# Net_Widget.net
KiCad netlist of a schematic drawn in EAGLE
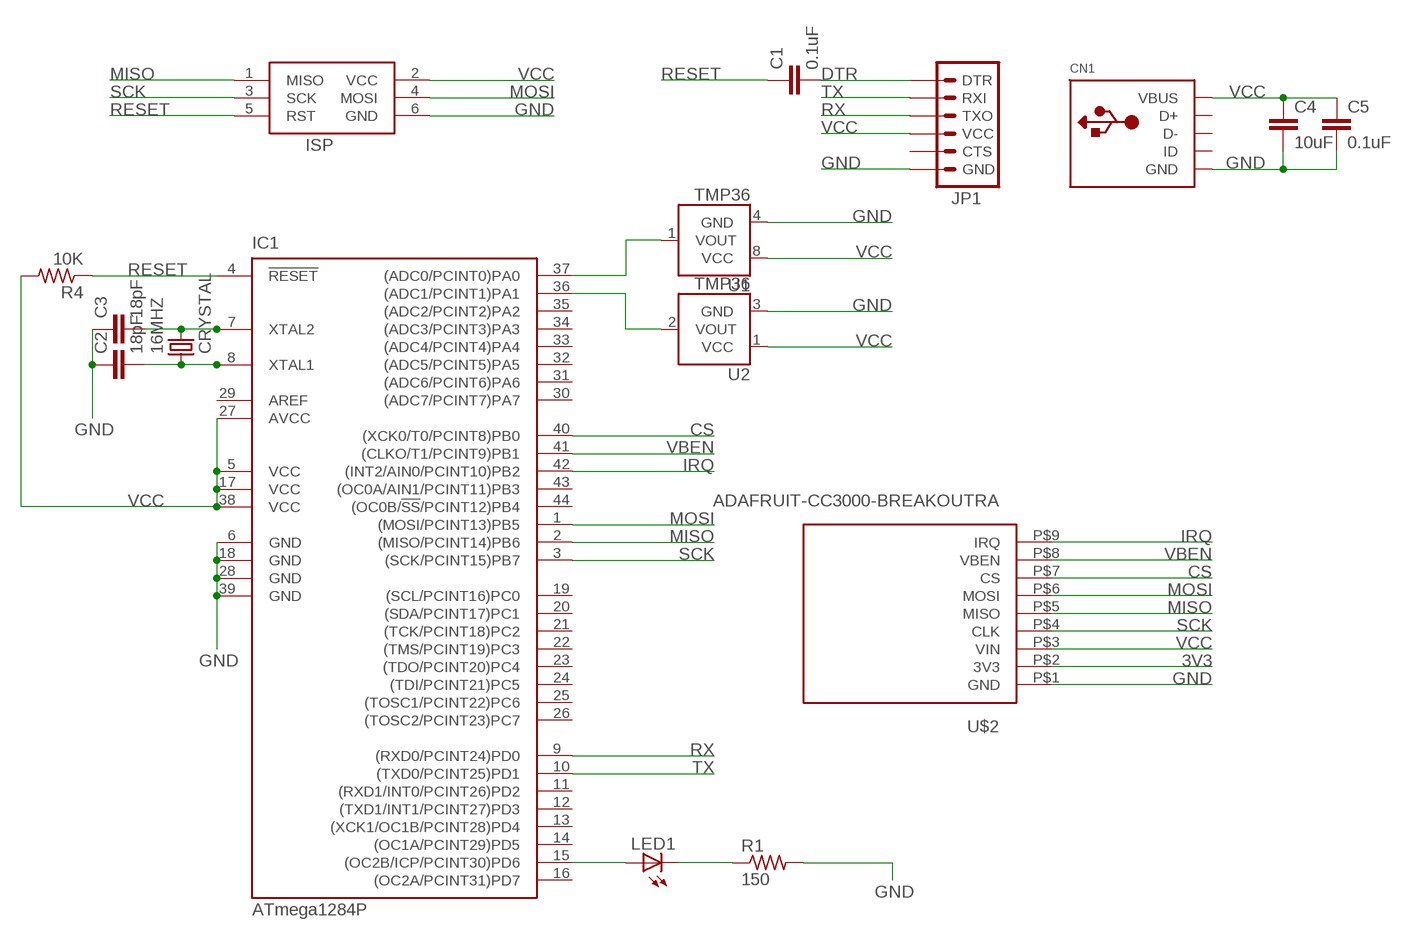
[diagram p0: schematic, sheet 1]

(export (version "E")
  (design (tool "Eeschema 10.0.6"))
  (components
    (comp (ref "16MHZ")
      (value "CRYSTAL")
      (footprint "eagle-import:2-SMD-5X3MM")
      (libsource (lib "eagle-import") (part "CRYSTAL"))
    )
    (comp (ref "C1")
      (value "0.1uF")
      (footprint "eagle-import:C1206")
      (libsource (lib "eagle-import") (part "C-EUC1206"))
    )
    (comp (ref "C2")
      (value "18pF")
      (footprint "eagle-import:C1206")
      (libsource (lib "eagle-import") (part "C-EUC1206"))
    )
    (comp (ref "C3")
      (value "18pF")
      (footprint "eagle-import:C1206")
      (libsource (lib "eagle-import") (part "C-EUC1206"))
    )
    (comp (ref "C4")
      (value "10uF")
      (footprint "eagle-import:C1206")
      (libsource (lib "eagle-import") (part "C-EUC1206"))
    )
    (comp (ref "C5")
      (value "0.1uF")
      (footprint "eagle-import:C1206")
      (libsource (lib "eagle-import") (part "C-EUC1206"))
    )
    (comp (ref "CN1")
      (value "USBPWR")
      (footprint "eagle-import:USB-MINIB-POWER")
      (libsource (lib "eagle-import") (part "USBPWR"))
    )
    (comp (ref "IC1")
      (value "ATmega1284P")
      (footprint "eagle-import:TQFP44")
      (libsource (lib "eagle-import") (part "MEGA164P/324P/644P-AU"))
    )
    (comp (ref "ISP")
      (value "AVRISP-6")
      (footprint "eagle-import:AVRISP")
      (libsource (lib "eagle-import") (part "AVRISP-6"))
    )
    (comp (ref "JP1")
      (value "ARDUINO_SERIAL_PROGRAMSMD")
      (footprint "eagle-import:1X06-SMD")
      (libsource (lib "eagle-import") (part "ARDUINO_SERIAL_PROGRAMSMD"))
    )
    (comp (ref "LED1")
      (value "LEDSMT1206")
      (footprint "eagle-import:1206")
      (libsource (lib "eagle-import") (part "LEDSMT1206"))
    )
    (comp (ref "R1")
      (value "150")
      (footprint "eagle-import:R1206")
      (libsource (lib "eagle-import") (part "R-US_R1206"))
    )
    (comp (ref "R4")
      (value "10K")
      (footprint "eagle-import:R1206")
      (libsource (lib "eagle-import") (part "R-US_R1206"))
    )
    (comp (ref "U$2")
      (value "ADAFRUIT-CC3000-BREAKOUTRA")
      (footprint "eagle-import:ADAFRUIT-CC3000-BREAKOUT-RA")
      (libsource (lib "eagle-import") (part "ADAFRUIT-CC3000-BREAKOUTRA"))
    )
    (comp (ref "U1")
      (value "TMP36")
      (footprint "eagle-import:SO08")
      (libsource (lib "eagle-import") (part "TMP36"))
    )
    (comp (ref "U2")
      (value "TMP36")
      (footprint "eagle-import:TO-92")
      (libsource (lib "eagle-import") (part "TMP36GT9"))
    )
  )
  (nets
    (net (code "1") (name "/3V3") (class "Default")
      (node (ref "U$2") (pin "P$2") (pinfunction "3V3_P$2") (pintype "bidirectional"))
    )
    (net (code "2") (name "/AREF") (class "Default")
      (node (ref "IC1") (pin "29") (pinfunction "AREF_29") (pintype "power_in"))
    )
    (net (code "3") (name "/CS") (class "Default")
      (node (ref "IC1") (pin "40") (pinfunction "(XCK0/T0/PCINT8)PB0_40") (pintype "bidirectional"))
      (node (ref "U$2") (pin "P$7") (pinfunction "CS_P$7") (pintype "bidirectional"))
    )
    (net (code "4") (name "/DTR") (class "Default")
      (node (ref "C1") (pin "2") (pinfunction "2_2") (pintype "passive"))
      (node (ref "JP1") (pin "1") (pinfunction "DTR_1") (pintype "passive"))
    )
    (net (code "5") (name "/GND") (class "Default")
      (node (ref "C2") (pin "1") (pinfunction "1_1") (pintype "passive"))
      (node (ref "C3") (pin "1") (pinfunction "1_1") (pintype "passive"))
      (node (ref "C4") (pin "2") (pinfunction "2_2") (pintype "passive"))
      (node (ref "C5") (pin "2") (pinfunction "2_2") (pintype "passive"))
      (node (ref "CN1") (pin "GND") (pinfunction "GND_GND") (pintype "power_in"))
      (node (ref "IC1") (pin "18") (pinfunction "GND_18") (pintype "power_in"))
      (node (ref "IC1") (pin "28") (pinfunction "GND_28") (pintype "power_in"))
      (node (ref "IC1") (pin "39") (pinfunction "GND_39") (pintype "power_in"))
      (node (ref "IC1") (pin "6") (pinfunction "GND_6") (pintype "power_in"))
      (node (ref "ISP") (pin "6") (pinfunction "GND_6") (pintype "power_in"))
      (node (ref "JP1") (pin "6") (pinfunction "GND_6") (pintype "passive"))
      (node (ref "R1") (pin "2") (pinfunction "2_2") (pintype "passive"))
      (node (ref "U$2") (pin "P$1") (pinfunction "GND_P$1") (pintype "bidirectional"))
      (node (ref "U1") (pin "4") (pinfunction "GND_4") (pintype "bidirectional"))
      (node (ref "U2") (pin "3") (pinfunction "GND_3") (pintype "bidirectional"))
    )
    (net (code "6") (name "/IRQ") (class "Default")
      (node (ref "IC1") (pin "42") (pinfunction "(INT2/AIN0/PCINT10)PB2_42") (pintype "bidirectional"))
      (node (ref "U$2") (pin "P$9") (pinfunction "IRQ_P$9") (pintype "bidirectional"))
    )
    (net (code "7") (name "/MISO") (class "Default")
      (node (ref "IC1") (pin "2") (pinfunction "(MISO/PCINT14)PB6_2") (pintype "bidirectional"))
      (node (ref "ISP") (pin "1") (pinfunction "MISO_1") (pintype "input"))
      (node (ref "U$2") (pin "P$5") (pinfunction "MISO_P$5") (pintype "bidirectional"))
    )
    (net (code "8") (name "/MOSI") (class "Default")
      (node (ref "IC1") (pin "1") (pinfunction "(MOSI/PCINT13)PB5_1") (pintype "bidirectional"))
      (node (ref "ISP") (pin "4") (pinfunction "MOSI_4") (pintype "output"))
      (node (ref "U$2") (pin "P$6") (pinfunction "MOSI_P$6") (pintype "bidirectional"))
    )
    (net (code "9") (name "/RESET") (class "Default")
      (node (ref "C1") (pin "1") (pinfunction "1_1") (pintype "passive"))
      (node (ref "IC1") (pin "4") (pinfunction "~{RESET}_4") (pintype "input"))
      (node (ref "ISP") (pin "5") (pinfunction "RST_5") (pintype "output"))
      (node (ref "R4") (pin "1") (pinfunction "1_1") (pintype "passive"))
    )
    (net (code "10") (name "/RX") (class "Default")
      (node (ref "IC1") (pin "9") (pinfunction "(RXD0/PCINT24)PD0_9") (pintype "bidirectional"))
      (node (ref "JP1") (pin "3") (pinfunction "TXO_3") (pintype "passive"))
    )
    (net (code "11") (name "/SCK") (class "Default")
      (node (ref "IC1") (pin "3") (pinfunction "(SCK/PCINT15)PB7_3") (pintype "bidirectional"))
      (node (ref "ISP") (pin "3") (pinfunction "SCK_3") (pintype "output"))
      (node (ref "U$2") (pin "P$4") (pinfunction "CLK_P$4") (pintype "bidirectional"))
    )
    (net (code "12") (name "/TX") (class "Default")
      (node (ref "IC1") (pin "10") (pinfunction "(TXD0/PCINT25)PD1_10") (pintype "bidirectional"))
      (node (ref "JP1") (pin "2") (pinfunction "RXI_2") (pintype "passive"))
    )
    (net (code "13") (name "/VBEN") (class "Default")
      (node (ref "IC1") (pin "41") (pinfunction "(CLKO/T1/PCINT9)PB1_41") (pintype "bidirectional"))
      (node (ref "U$2") (pin "P$8") (pinfunction "VBEN_P$8") (pintype "bidirectional"))
    )
    (net (code "14") (name "/VCC") (class "Default")
      (node (ref "C4") (pin "1") (pinfunction "1_1") (pintype "passive"))
      (node (ref "C5") (pin "1") (pinfunction "1_1") (pintype "passive"))
      (node (ref "CN1") (pin "VBUS") (pinfunction "VBUS_VBUS") (pintype "power_in"))
      (node (ref "IC1") (pin "17") (pinfunction "VCC_17") (pintype "power_in"))
      (node (ref "IC1") (pin "27") (pinfunction "AVCC_27") (pintype "power_in"))
      (node (ref "IC1") (pin "38") (pinfunction "VCC_38") (pintype "power_in"))
      (node (ref "IC1") (pin "5") (pinfunction "VCC_5") (pintype "power_in"))
      (node (ref "ISP") (pin "2") (pinfunction "VCC_2") (pintype "power_in"))
      (node (ref "JP1") (pin "4") (pinfunction "VCC_4") (pintype "passive"))
      (node (ref "R4") (pin "2") (pinfunction "2_2") (pintype "passive"))
      (node (ref "U$2") (pin "P$3") (pinfunction "VIN_P$3") (pintype "bidirectional"))
      (node (ref "U1") (pin "8") (pinfunction "VCC_8") (pintype "bidirectional"))
      (node (ref "U2") (pin "1") (pinfunction "VCC_1") (pintype "bidirectional"))
    )
    (net (code "15") (name "Net-(16MHZ-1)") (class "Default")
      (node (ref "16MHZ") (pin "P$1") (pinfunction "1_P$1") (pintype "passive"))
      (node (ref "C2") (pin "2") (pinfunction "2_2") (pintype "passive"))
      (node (ref "IC1") (pin "8") (pinfunction "XTAL1_8") (pintype "input"))
    )
    (net (code "16") (name "Net-(16MHZ-2)") (class "Default")
      (node (ref "16MHZ") (pin "P$2") (pinfunction "2_P$2") (pintype "passive"))
      (node (ref "C3") (pin "2") (pinfunction "2_2") (pintype "passive"))
      (node (ref "IC1") (pin "7") (pinfunction "XTAL2_7") (pintype "output"))
    )
    (net (code "17") (name "Net-(IC1-(ADC0{slash}PCINT0)PA0)") (class "Default")
      (node (ref "IC1") (pin "37") (pinfunction "(ADC0/PCINT0)PA0_37") (pintype "bidirectional"))
      (node (ref "U1") (pin "1") (pinfunction "VOUT_1") (pintype "bidirectional"))
    )
    (net (code "18") (name "Net-(IC1-(ADC1{slash}PCINT1)PA1)") (class "Default")
      (node (ref "IC1") (pin "36") (pinfunction "(ADC1/PCINT1)PA1_36") (pintype "bidirectional"))
      (node (ref "U2") (pin "2") (pinfunction "VOUT_2") (pintype "bidirectional"))
    )
    (net (code "19") (name "Net-(IC1-(OC2B{slash}ICP{slash}PCINT30)PD6)") (class "Default")
      (node (ref "IC1") (pin "15") (pinfunction "(OC2B/ICP/PCINT30)PD6_15") (pintype "bidirectional"))
      (node (ref "LED1") (pin "A") (pinfunction "A_A") (pintype "passive"))
    )
    (net (code "20") (name "Net-(LED1-PadC)") (class "Default")
      (node (ref "LED1") (pin "C") (pinfunction "C_C") (pintype "passive"))
      (node (ref "R1") (pin "1") (pinfunction "1_1") (pintype "passive"))
    )
    (net (code "21") (name "unconnected-(CN1-PadD+)") (class "Default")
      (node (ref "CN1") (pin "D+") (pinfunction "D+_D+") (pintype "bidirectional"))
    )
    (net (code "22") (name "unconnected-(CN1-PadD-)") (class "Default")
      (node (ref "CN1") (pin "D-") (pinfunction "D-_D-") (pintype "bidirectional"))
    )
    (net (code "23") (name "unconnected-(CN1-PadID)") (class "Default")
      (node (ref "CN1") (pin "ID") (pinfunction "ID_ID") (pintype "bidirectional"))
    )
    (net (code "24") (name "unconnected-(IC1-(ADC2{slash}PCINT2)PA2-Pad35)") (class "Default")
      (node (ref "IC1") (pin "35") (pinfunction "(ADC2/PCINT2)PA2_35") (pintype "bidirectional"))
    )
    (net (code "25") (name "unconnected-(IC1-(ADC3{slash}PCINT3)PA3-Pad34)") (class "Default")
      (node (ref "IC1") (pin "34") (pinfunction "(ADC3/PCINT3)PA3_34") (pintype "bidirectional"))
    )
    (net (code "26") (name "unconnected-(IC1-(ADC4{slash}PCINT4)PA4-Pad33)") (class "Default")
      (node (ref "IC1") (pin "33") (pinfunction "(ADC4/PCINT4)PA4_33") (pintype "bidirectional"))
    )
    (net (code "27") (name "unconnected-(IC1-(ADC5{slash}PCINT5)PA5-Pad32)") (class "Default")
      (node (ref "IC1") (pin "32") (pinfunction "(ADC5/PCINT5)PA5_32") (pintype "bidirectional"))
    )
    (net (code "28") (name "unconnected-(IC1-(ADC6{slash}PCINT6)PA6-Pad31)") (class "Default")
      (node (ref "IC1") (pin "31") (pinfunction "(ADC6/PCINT6)PA6_31") (pintype "bidirectional"))
    )
    (net (code "29") (name "unconnected-(IC1-(ADC7{slash}PCINT7)PA7-Pad30)") (class "Default")
      (node (ref "IC1") (pin "30") (pinfunction "(ADC7/PCINT7)PA7_30") (pintype "bidirectional"))
    )
    (net (code "30") (name "unconnected-(IC1-(OC0A{slash}AIN1{slash}PCINT11)PB3-Pad43)") (class "Default")
      (node (ref "IC1") (pin "43") (pinfunction "(OC0A/AIN1/PCINT11)PB3_43") (pintype "bidirectional"))
    )
    (net (code "31") (name "unconnected-(IC1-(OC0B{slash}~{SS}{slash}PCINT12)PB4-Pad44)") (class "Default")
      (node (ref "IC1") (pin "44") (pinfunction "(OC0B/~{SS}/PCINT12)PB4_44") (pintype "bidirectional"))
    )
    (net (code "32") (name "unconnected-(IC1-(OC1A{slash}PCINT29)PD5-Pad14)") (class "Default")
      (node (ref "IC1") (pin "14") (pinfunction "(OC1A/PCINT29)PD5_14") (pintype "bidirectional"))
    )
    (net (code "33") (name "unconnected-(IC1-(OC2A{slash}PCINT31)PD7-Pad16)") (class "Default")
      (node (ref "IC1") (pin "16") (pinfunction "(OC2A/PCINT31)PD7_16") (pintype "bidirectional"))
    )
    (net (code "34") (name "unconnected-(IC1-(RXD1{slash}INT0{slash}PCINT26)PD2-Pad11)") (class "Default")
      (node (ref "IC1") (pin "11") (pinfunction "(RXD1/INT0/PCINT26)PD2_11") (pintype "bidirectional"))
    )
    (net (code "35") (name "unconnected-(IC1-(SCL{slash}PCINT16)PC0-Pad19)") (class "Default")
      (node (ref "IC1") (pin "19") (pinfunction "(SCL/PCINT16)PC0_19") (pintype "bidirectional"))
    )
    (net (code "36") (name "unconnected-(IC1-(SDA{slash}PCINT17)PC1-Pad20)") (class "Default")
      (node (ref "IC1") (pin "20") (pinfunction "(SDA/PCINT17)PC1_20") (pintype "bidirectional"))
    )
    (net (code "37") (name "unconnected-(IC1-(TCK{slash}PCINT18)PC2-Pad21)") (class "Default")
      (node (ref "IC1") (pin "21") (pinfunction "(TCK/PCINT18)PC2_21") (pintype "bidirectional"))
    )
    (net (code "38") (name "unconnected-(IC1-(TDI{slash}PCINT21)PC5-Pad24)") (class "Default")
      (node (ref "IC1") (pin "24") (pinfunction "(TDI/PCINT21)PC5_24") (pintype "bidirectional"))
    )
    (net (code "39") (name "unconnected-(IC1-(TDO{slash}PCINT20)PC4-Pad23)") (class "Default")
      (node (ref "IC1") (pin "23") (pinfunction "(TDO/PCINT20)PC4_23") (pintype "bidirectional"))
    )
    (net (code "40") (name "unconnected-(IC1-(TMS{slash}PCINT19)PC3-Pad22)") (class "Default")
      (node (ref "IC1") (pin "22") (pinfunction "(TMS/PCINT19)PC3_22") (pintype "bidirectional"))
    )
    (net (code "41") (name "unconnected-(IC1-(TOSC1{slash}PCINT22)PC6-Pad25)") (class "Default")
      (node (ref "IC1") (pin "25") (pinfunction "(TOSC1/PCINT22)PC6_25") (pintype "bidirectional"))
    )
    (net (code "42") (name "unconnected-(IC1-(TOSC2{slash}PCINT23)PC7-Pad26)") (class "Default")
      (node (ref "IC1") (pin "26") (pinfunction "(TOSC2/PCINT23)PC7_26") (pintype "bidirectional"))
    )
    (net (code "43") (name "unconnected-(IC1-(TXD1{slash}INT1{slash}PCINT27)PD3-Pad12)") (class "Default")
      (node (ref "IC1") (pin "12") (pinfunction "(TXD1/INT1/PCINT27)PD3_12") (pintype "bidirectional"))
    )
    (net (code "44") (name "unconnected-(IC1-(XCK1{slash}OC1B{slash}PCINT28)PD4-Pad13)") (class "Default")
      (node (ref "IC1") (pin "13") (pinfunction "(XCK1/OC1B/PCINT28)PD4_13") (pintype "bidirectional"))
    )
    (net (code "45") (name "unconnected-(JP1-CTS-Pad5)") (class "Default")
      (node (ref "JP1") (pin "5") (pinfunction "CTS_5") (pintype "passive"))
    )
  )
)
